# Clavier.net
KiCad netlist of a schematic drawn in Altium Designer
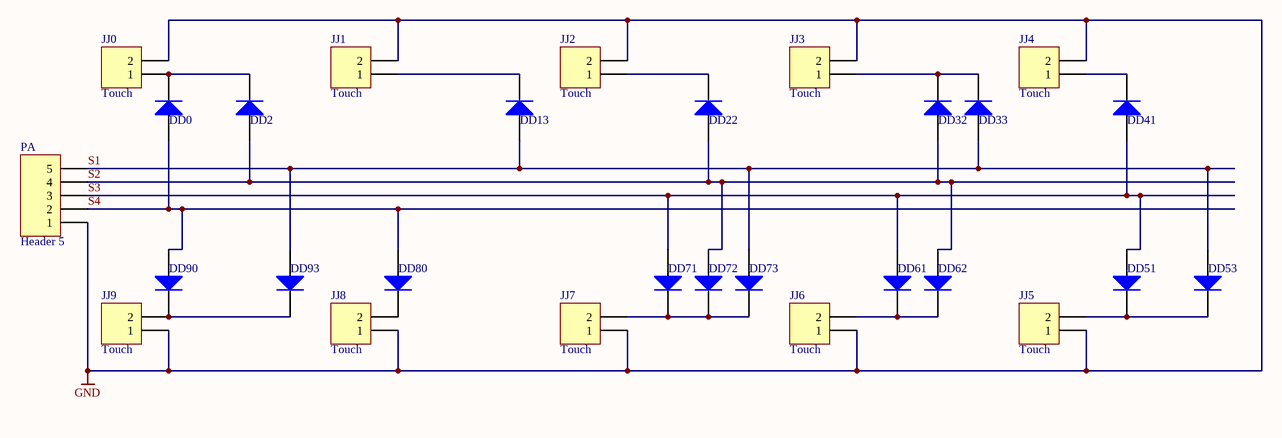
[diagram p0: Clavier.SchDoc]

(export (version "E")
  (design (tool "Eeschema 10.0.6"))
  (components
    (comp (ref "DD0")
      (value "BAV103")
      (footprint "SOD80C")
      (description "General-purpose Diode")
      (fields (field (name "PUBLISHER") "Altium Limited"))
      (libsource (lib "Philips Discrete Diode - Switching") (part "BAV103"))
    )
    (comp (ref "DD2")
      (value "BAV103")
      (footprint "SOD80C")
      (description "General-purpose Diode")
      (fields (field (name "PUBLISHER") "Altium Limited"))
      (libsource (lib "Philips Discrete Diode - Switching") (part "BAV103"))
    )
    (comp (ref "DD13")
      (value "BAV103")
      (footprint "SOD80C")
      (description "General-purpose Diode")
      (fields (field (name "PUBLISHER") "Altium Limited"))
      (libsource (lib "Philips Discrete Diode - Switching") (part "BAV103"))
    )
    (comp (ref "DD22")
      (value "BAV103")
      (footprint "SOD80C")
      (description "General-purpose Diode")
      (fields (field (name "PUBLISHER") "Altium Limited"))
      (libsource (lib "Philips Discrete Diode - Switching") (part "BAV103"))
    )
    (comp (ref "DD32")
      (value "BAV103")
      (footprint "SOD80C")
      (description "General-purpose Diode")
      (fields (field (name "PUBLISHER") "Altium Limited"))
      (libsource (lib "Philips Discrete Diode - Switching") (part "BAV103"))
    )
    (comp (ref "DD33")
      (value "BAV103")
      (footprint "SOD80C")
      (description "General-purpose Diode")
      (fields (field (name "PUBLISHER") "Altium Limited"))
      (libsource (lib "Philips Discrete Diode - Switching") (part "BAV103"))
    )
    (comp (ref "DD41")
      (value "BAV103")
      (footprint "SOD80C")
      (description "General-purpose Diode")
      (fields (field (name "PUBLISHER") "Altium Limited"))
      (libsource (lib "Philips Discrete Diode - Switching") (part "BAV103"))
    )
    (comp (ref "DD51")
      (value "BAV103")
      (footprint "SOD80C")
      (description "General-purpose Diode")
      (fields (field (name "PUBLISHER") "Altium Limited"))
      (libsource (lib "Philips Discrete Diode - Switching") (part "BAV103"))
    )
    (comp (ref "DD53")
      (value "BAV103")
      (footprint "SOD80C")
      (description "General-purpose Diode")
      (fields (field (name "PUBLISHER") "Altium Limited"))
      (libsource (lib "Philips Discrete Diode - Switching") (part "BAV103"))
    )
    (comp (ref "DD61")
      (value "BAV103")
      (footprint "SOD80C")
      (description "General-purpose Diode")
      (fields (field (name "PUBLISHER") "Altium Limited"))
      (libsource (lib "Philips Discrete Diode - Switching") (part "BAV103"))
    )
    (comp (ref "DD62")
      (value "BAV103")
      (footprint "SOD80C")
      (description "General-purpose Diode")
      (fields (field (name "PUBLISHER") "Altium Limited"))
      (libsource (lib "Philips Discrete Diode - Switching") (part "BAV103"))
    )
    (comp (ref "DD71")
      (value "BAV103")
      (footprint "SOD80C")
      (description "General-purpose Diode")
      (fields (field (name "PUBLISHER") "Altium Limited"))
      (libsource (lib "Philips Discrete Diode - Switching") (part "BAV103"))
    )
    (comp (ref "DD72")
      (value "BAV103")
      (footprint "SOD80C")
      (description "General-purpose Diode")
      (fields (field (name "PUBLISHER") "Altium Limited"))
      (libsource (lib "Philips Discrete Diode - Switching") (part "BAV103"))
    )
    (comp (ref "DD73")
      (value "BAV103")
      (footprint "SOD80C")
      (description "General-purpose Diode")
      (fields (field (name "PUBLISHER") "Altium Limited"))
      (libsource (lib "Philips Discrete Diode - Switching") (part "BAV103"))
    )
    (comp (ref "DD80")
      (value "BAV103")
      (footprint "SOD80C")
      (description "General-purpose Diode")
      (fields (field (name "PUBLISHER") "Altium Limited"))
      (libsource (lib "Philips Discrete Diode - Switching") (part "BAV103"))
    )
    (comp (ref "DD90")
      (value "BAV103")
      (footprint "SOD80C")
      (description "General-purpose Diode")
      (fields (field (name "PUBLISHER") "Altium Limited"))
      (libsource (lib "Philips Discrete Diode - Switching") (part "BAV103"))
    )
    (comp (ref "DD93")
      (value "BAV103")
      (footprint "SOD80C")
      (description "General-purpose Diode")
      (fields (field (name "PUBLISHER") "Altium Limited"))
      (libsource (lib "Philips Discrete Diode - Switching") (part "BAV103"))
    )
    (comp (ref "JJ0")
      (value "Touch")
      (footprint "HDR1X2")
      (description "Header, 2-Pin")
      (fields (field (name "PUBLISHER") "Altium Limited"))
      (libsource (lib "Miscellaneous Connectors") (part "Header 2"))
    )
    (comp (ref "JJ1")
      (value "Touch")
      (footprint "HDR1X2")
      (description "Header, 2-Pin")
      (fields (field (name "PUBLISHER") "Altium Limited"))
      (libsource (lib "Miscellaneous Connectors") (part "Header 2"))
    )
    (comp (ref "JJ2")
      (value "Touch")
      (footprint "HDR1X2")
      (description "Header, 2-Pin")
      (fields (field (name "PUBLISHER") "Altium Limited"))
      (libsource (lib "Miscellaneous Connectors") (part "Header 2"))
    )
    (comp (ref "JJ3")
      (value "Touch")
      (footprint "HDR1X2")
      (description "Header, 2-Pin")
      (fields (field (name "PUBLISHER") "Altium Limited"))
      (libsource (lib "Miscellaneous Connectors") (part "Header 2"))
    )
    (comp (ref "JJ4")
      (value "Touch")
      (footprint "HDR1X2")
      (description "Header, 2-Pin")
      (fields (field (name "PUBLISHER") "Altium Limited"))
      (libsource (lib "Miscellaneous Connectors") (part "Header 2"))
    )
    (comp (ref "JJ5")
      (value "Touch")
      (footprint "HDR1X2")
      (description "Header, 2-Pin")
      (fields (field (name "PUBLISHER") "Altium Limited"))
      (libsource (lib "Miscellaneous Connectors") (part "Header 2"))
    )
    (comp (ref "JJ6")
      (value "Touch")
      (footprint "HDR1X2")
      (description "Header, 2-Pin")
      (fields (field (name "PUBLISHER") "Altium Limited"))
      (libsource (lib "Miscellaneous Connectors") (part "Header 2"))
    )
    (comp (ref "JJ7")
      (value "Touch")
      (footprint "HDR1X2")
      (description "Header, 2-Pin")
      (fields (field (name "PUBLISHER") "Altium Limited"))
      (libsource (lib "Miscellaneous Connectors") (part "Header 2"))
    )
    (comp (ref "JJ8")
      (value "Touch")
      (footprint "HDR1X2")
      (description "Header, 2-Pin")
      (fields (field (name "PUBLISHER") "Altium Limited"))
      (libsource (lib "Miscellaneous Connectors") (part "Header 2"))
    )
    (comp (ref "JJ9")
      (value "Touch")
      (footprint "HDR1X2")
      (description "Header, 2-Pin")
      (fields (field (name "PUBLISHER") "Altium Limited"))
      (libsource (lib "Miscellaneous Connectors") (part "Header 2"))
    )
    (comp (ref "PA")
      (value "Header 5")
      (footprint "HDR1X5")
      (description "Header, 5-Pin")
      (fields (field (name "PUBLISHER") "Altium Limited"))
      (libsource (lib "Miscellaneous Connectors") (part "Header 5"))
    )
  )
  (nets
    (net (code "1") (name "/S1") (class "Default")
      (node (ref "DD13") (pin "1") (pinfunction "A_1") (pintype "passive"))
      (node (ref "DD33") (pin "1") (pinfunction "A_1") (pintype "passive"))
      (node (ref "DD53") (pin "1") (pinfunction "A_1") (pintype "passive"))
      (node (ref "DD73") (pin "1") (pinfunction "A_1") (pintype "passive"))
      (node (ref "DD93") (pin "1") (pinfunction "A_1") (pintype "passive"))
      (node (ref "PA") (pin "5") (pinfunction "5_5") (pintype "passive"))
    )
    (net (code "2") (name "/S2") (class "Default")
      (node (ref "DD2") (pin "1") (pinfunction "A_1") (pintype "passive"))
      (node (ref "DD22") (pin "1") (pinfunction "A_1") (pintype "passive"))
      (node (ref "DD32") (pin "1") (pinfunction "A_1") (pintype "passive"))
      (node (ref "DD62") (pin "1") (pinfunction "A_1") (pintype "passive"))
      (node (ref "DD72") (pin "1") (pinfunction "A_1") (pintype "passive"))
      (node (ref "PA") (pin "4") (pinfunction "4_4") (pintype "passive"))
    )
    (net (code "3") (name "/S3") (class "Default")
      (node (ref "DD41") (pin "1") (pinfunction "A_1") (pintype "passive"))
      (node (ref "DD51") (pin "1") (pinfunction "A_1") (pintype "passive"))
      (node (ref "DD61") (pin "1") (pinfunction "A_1") (pintype "passive"))
      (node (ref "DD71") (pin "1") (pinfunction "A_1") (pintype "passive"))
      (node (ref "PA") (pin "3") (pinfunction "3_3") (pintype "passive"))
    )
    (net (code "4") (name "/S4") (class "Default")
      (node (ref "DD0") (pin "1") (pinfunction "A_1") (pintype "passive"))
      (node (ref "DD80") (pin "1") (pinfunction "A_1") (pintype "passive"))
      (node (ref "DD90") (pin "1") (pinfunction "A_1") (pintype "passive"))
      (node (ref "PA") (pin "2") (pinfunction "2_2") (pintype "passive"))
    )
    (net (code "5") (name "GND") (class "Default")
      (node (ref "JJ0") (pin "2") (pinfunction "2_2") (pintype "passive"))
      (node (ref "JJ1") (pin "2") (pinfunction "2_2") (pintype "passive"))
      (node (ref "JJ2") (pin "2") (pinfunction "2_2") (pintype "passive"))
      (node (ref "JJ3") (pin "2") (pinfunction "2_2") (pintype "passive"))
      (node (ref "JJ4") (pin "2") (pinfunction "2_2") (pintype "passive"))
      (node (ref "JJ5") (pin "1") (pinfunction "1_1") (pintype "passive"))
      (node (ref "JJ6") (pin "1") (pinfunction "1_1") (pintype "passive"))
      (node (ref "JJ7") (pin "1") (pinfunction "1_1") (pintype "passive"))
      (node (ref "JJ8") (pin "1") (pinfunction "1_1") (pintype "passive"))
      (node (ref "JJ9") (pin "1") (pinfunction "1_1") (pintype "passive"))
      (node (ref "PA") (pin "1") (pinfunction "1_1") (pintype "passive"))
    )
    (net (code "6") (name "Net-(DD0-K)") (class "Default")
      (node (ref "DD0") (pin "2") (pinfunction "K_2") (pintype "passive"))
      (node (ref "DD2") (pin "2") (pinfunction "K_2") (pintype "passive"))
      (node (ref "JJ0") (pin "1") (pinfunction "1_1") (pintype "passive"))
    )
    (net (code "7") (name "Net-(DD13-K)") (class "Default")
      (node (ref "DD13") (pin "2") (pinfunction "K_2") (pintype "passive"))
      (node (ref "JJ1") (pin "1") (pinfunction "1_1") (pintype "passive"))
    )
    (net (code "8") (name "Net-(DD22-K)") (class "Default")
      (node (ref "DD22") (pin "2") (pinfunction "K_2") (pintype "passive"))
      (node (ref "JJ2") (pin "1") (pinfunction "1_1") (pintype "passive"))
    )
    (net (code "9") (name "Net-(DD32-K)") (class "Default")
      (node (ref "DD32") (pin "2") (pinfunction "K_2") (pintype "passive"))
      (node (ref "DD33") (pin "2") (pinfunction "K_2") (pintype "passive"))
      (node (ref "JJ3") (pin "1") (pinfunction "1_1") (pintype "passive"))
    )
    (net (code "10") (name "Net-(DD41-K)") (class "Default")
      (node (ref "DD41") (pin "2") (pinfunction "K_2") (pintype "passive"))
      (node (ref "JJ4") (pin "1") (pinfunction "1_1") (pintype "passive"))
    )
    (net (code "11") (name "Net-(DD51-K)") (class "Default")
      (node (ref "DD51") (pin "2") (pinfunction "K_2") (pintype "passive"))
      (node (ref "DD53") (pin "2") (pinfunction "K_2") (pintype "passive"))
      (node (ref "JJ5") (pin "2") (pinfunction "2_2") (pintype "passive"))
    )
    (net (code "12") (name "Net-(DD61-K)") (class "Default")
      (node (ref "DD61") (pin "2") (pinfunction "K_2") (pintype "passive"))
      (node (ref "DD62") (pin "2") (pinfunction "K_2") (pintype "passive"))
      (node (ref "JJ6") (pin "2") (pinfunction "2_2") (pintype "passive"))
    )
    (net (code "13") (name "Net-(DD71-K)") (class "Default")
      (node (ref "DD71") (pin "2") (pinfunction "K_2") (pintype "passive"))
      (node (ref "DD72") (pin "2") (pinfunction "K_2") (pintype "passive"))
      (node (ref "DD73") (pin "2") (pinfunction "K_2") (pintype "passive"))
      (node (ref "JJ7") (pin "2") (pinfunction "2_2") (pintype "passive"))
    )
    (net (code "14") (name "Net-(DD80-K)") (class "Default")
      (node (ref "DD80") (pin "2") (pinfunction "K_2") (pintype "passive"))
      (node (ref "JJ8") (pin "2") (pinfunction "2_2") (pintype "passive"))
    )
    (net (code "15") (name "Net-(DD90-K)") (class "Default")
      (node (ref "DD90") (pin "2") (pinfunction "K_2") (pintype "passive"))
      (node (ref "DD93") (pin "2") (pinfunction "K_2") (pintype "passive"))
      (node (ref "JJ9") (pin "2") (pinfunction "2_2") (pintype "passive"))
    )
  )
)
